# Sheet4.net
KiCad netlist of a schematic drawn in Altium Designer
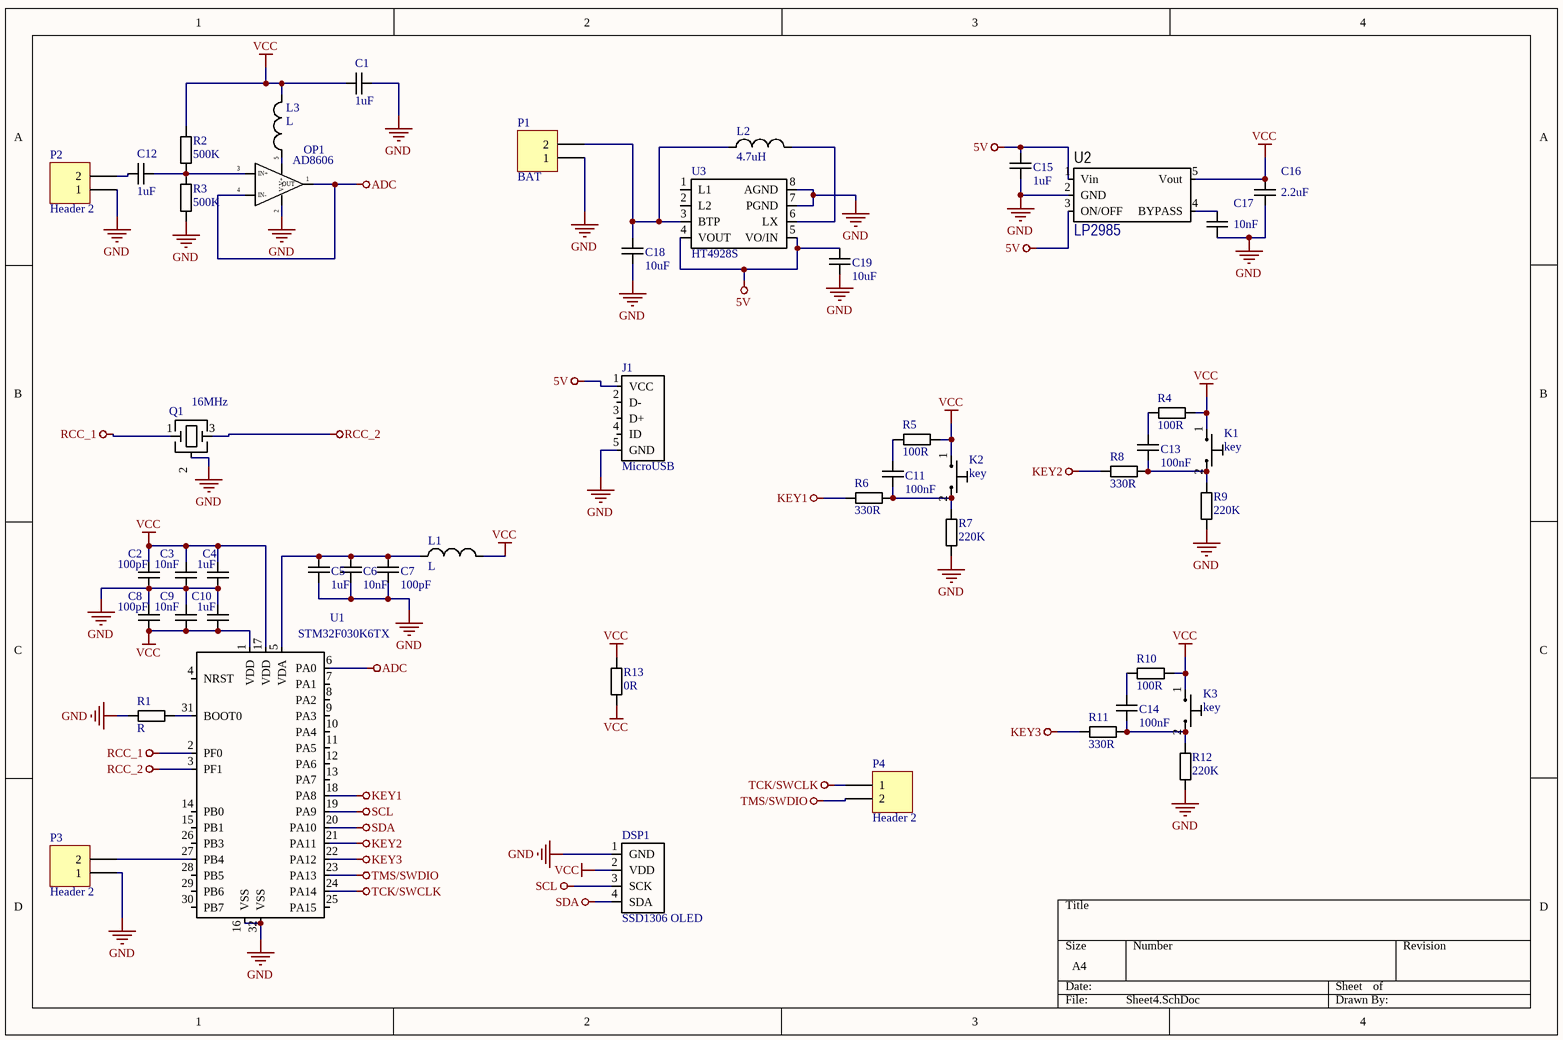
[diagram p0: Sheet4.SchDoc]

(export (version "E")
  (design (tool "Eeschema 10.0.6"))
  (components
    (comp (ref "C1") (value "1uF") (footprint "SMD-0402C") (libsource (lib "Schlib2") (part "С")))
    (comp (ref "C2") (value "100pF") (footprint "SMD-0402C") (libsource (lib "Schlib2") (part "С")))
    (comp (ref "C3") (value "10nF") (footprint "SMD-0402C") (libsource (lib "Schlib2") (part "С")))
    (comp (ref "C4") (value "1uF") (footprint "SMD-0402C") (libsource (lib "Schlib2") (part "С")))
    (comp (ref "C5") (value "1uF") (footprint "SMD-0402C") (libsource (lib "Schlib2") (part "С")))
    (comp (ref "C6") (value "10nF") (footprint "SMD-0402C") (libsource (lib "Schlib2") (part "С")))
    (comp (ref "C7") (value "100pF") (footprint "SMD-0402C") (libsource (lib "Schlib2") (part "С")))
    (comp (ref "C8") (value "100pF") (footprint "SMD-0402C") (libsource (lib "Schlib2") (part "С")))
    (comp (ref "C9") (value "10nF") (footprint "SMD-0402C") (libsource (lib "Schlib2") (part "С")))
    (comp (ref "C10") (value "1uF") (footprint "SMD-0402C") (libsource (lib "Schlib2") (part "С")))
    (comp (ref "C11") (value "100nF") (footprint "SMD-0402C") (libsource (lib "Schlib2") (part "С")))
    (comp (ref "C12") (value "1uF") (footprint "SMD-0402C") (libsource (lib "Schlib2") (part "С")))
    (comp (ref "C13") (value "100nF") (footprint "SMD-0402C") (libsource (lib "Schlib2") (part "С")))
    (comp (ref "C14") (value "100nF") (footprint "SMD-0402C") (libsource (lib "Schlib2") (part "С")))
    (comp (ref "C15") (value "1uF") (footprint "SMD-0402C") (libsource (lib "Schlib2") (part "С")))
    (comp (ref "C16") (value "2.2uF") (footprint "SMD-0402C") (libsource (lib "Schlib2") (part "С")))
    (comp (ref "C17") (value "10nF") (footprint "SMD-0402C") (libsource (lib "Schlib2") (part "С")))
    (comp (ref "C18") (value "10uF") (footprint "SMD-0805C") (libsource (lib "Schlib2") (part "С")))
    (comp (ref "C19") (value "10uF") (footprint "SMD-0805C") (libsource (lib "Schlib2") (part "С")))
    (comp (ref "DSP1")
      (value "SSD1306 OLED")
      (footprint "SSD1306")
      (libsource (lib "Schlib2") (part "SSD1306_OLED"))
    )
    (comp (ref "J1")
      (value "MicroUSB")
      (footprint "Micro USB")
      (libsource (lib "Schlib2") (part "Micro_USB_female"))
    )
    (comp (ref "K1") (value "key") (footprint "KEY") (libsource (lib "Schlib2") (part "KEY")))
    (comp (ref "K2") (value "key") (footprint "KEY") (libsource (lib "Schlib2") (part "KEY")))
    (comp (ref "K3") (value "key") (footprint "KEY") (libsource (lib "Schlib2") (part "KEY")))
    (comp (ref "L1") (value "L") (footprint "L_0805") (libsource (lib "Schlib2") (part "L")))
    (comp (ref "L2") (value "4.7uH") (footprint "CD43") (libsource (lib "Schlib2") (part "L")))
    (comp (ref "L3") (value "L") (footprint "L_0805") (libsource (lib "Schlib2") (part "L")))
    (comp (ref "OP1") (value "AD8606") (footprint "SOT-23-5") (libsource (lib "Schlib2") (part "AD8605")))
    (comp (ref "P1")
      (value "BAT")
      (footprint "MHDR1X2")
      (description "Header, 2-Pin")
      (fields (field (name "PUBLISHER") "Altium Limited"))
      (libsource (lib "Miscellaneous Connectors") (part "MHDR1X2"))
    )
    (comp (ref "P2")
      (value "Header 2")
      (footprint "HDR1X2")
      (description "Header, 2-Pin")
      (fields (field (name "PUBLISHER") "Altium Limited"))
      (libsource (lib "Miscellaneous Connectors") (part "Header 2"))
    )
    (comp (ref "P3")
      (value "Header 2")
      (footprint "HDR1X2")
      (description "Header, 2-Pin")
      (fields (field (name "PUBLISHER") "Altium Limited"))
      (libsource (lib "Miscellaneous Connectors") (part "Header 2"))
    )
    (comp (ref "P4")
      (value "Header 2")
      (footprint "HDR1X2")
      (description "Header, 2-Pin")
      (fields (field (name "PUBLISHER") "Altium Limited"))
      (libsource (lib "") (part "Header 2_1"))
    )
    (comp (ref "Q1")
      (value "16MHz")
      (footprint "Murata Ceramic Resonator")
      (libsource (lib "Schlib2") (part "Crystal_3"))
    )
    (comp (ref "R1") (value "R") (footprint "SMD-0402-RES") (libsource (lib "Schlib2") (part "R")))
    (comp (ref "R2") (value "500K") (footprint "SMD-0402-RES") (libsource (lib "Schlib2") (part "R")))
    (comp (ref "R3") (value "500K") (footprint "SMD-0402-RES") (libsource (lib "Schlib2") (part "R")))
    (comp (ref "R4") (value "100R") (footprint "SMD-0402-RES") (libsource (lib "Schlib2") (part "R")))
    (comp (ref "R5") (value "100R") (footprint "SMD-0402-RES") (libsource (lib "Schlib2") (part "R")))
    (comp (ref "R6") (value "330R") (footprint "SMD-0402-RES") (libsource (lib "Schlib2") (part "R")))
    (comp (ref "R7") (value "220K") (footprint "SMD-0402-RES") (libsource (lib "Schlib2") (part "R")))
    (comp (ref "R8") (value "330R") (footprint "SMD-0402-RES") (libsource (lib "Schlib2") (part "R")))
    (comp (ref "R9") (value "220K") (footprint "SMD-0402-RES") (libsource (lib "Schlib2") (part "R")))
    (comp (ref "R10") (value "100R") (footprint "SMD-0402-RES") (libsource (lib "Schlib2") (part "R")))
    (comp (ref "R11") (value "330R") (footprint "SMD-0402-RES") (libsource (lib "Schlib2") (part "R")))
    (comp (ref "R12") (value "220K") (footprint "SMD-0402-RES") (libsource (lib "Schlib2") (part "R")))
    (comp (ref "R13") (value "0R") (footprint "SMD-0805-RES") (libsource (lib "Schlib2") (part "R")))
    (comp (ref "U1")
      (value "STM32F030K6TX")
      (footprint "LQFP-32")
      (libsource (lib "Schlib2") (part "STM32F030K6TX"))
    )
    (comp (ref "U2") (value "LP2985") (footprint "SOT-23-5") (libsource (lib "Schlib2") (part "LP2985")))
    (comp (ref "U3") (value "HT4928S") (footprint "SOIC8") (libsource (lib "Schlib2") (part "HT4928S")))
  )
  (nets
    (net (code "1") (name "5V") (class "Default")
      (node (ref "C15") (pin "2") (pinfunction "2_2") (pintype "passive"))
      (node (ref "C19") (pin "1") (pinfunction "1_1") (pintype "passive"))
      (node (ref "J1") (pin "1") (pinfunction "VCC_1") (pintype "passive"))
      (node (ref "U2") (pin "1") (pinfunction "Vin_1") (pintype "passive"))
      (node (ref "U2") (pin "3") (pinfunction "ON/OFF_3") (pintype "passive"))
      (node (ref "U3") (pin "4") (pinfunction "VOUT_4") (pintype "passive"))
      (node (ref "U3") (pin "5") (pinfunction "VO/IN_5") (pintype "passive"))
    )
    (net (code "2") (name "ADC") (class "Default")
      (node (ref "OP1") (pin "1") (pinfunction "OUT_1") (pintype "passive"))
      (node (ref "OP1") (pin "4") (pinfunction "IN-_4") (pintype "passive"))
      (node (ref "U1") (pin "6") (pinfunction "PA0_6") (pintype "passive"))
    )
    (net (code "3") (name "GND") (class "Default")
      (node (ref "C1") (pin "1") (pinfunction "1_1") (pintype "passive"))
      (node (ref "C10") (pin "2") (pinfunction "2_2") (pintype "passive"))
      (node (ref "C15") (pin "1") (pinfunction "1_1") (pintype "passive"))
      (node (ref "C16") (pin "1") (pinfunction "1_1") (pintype "passive"))
      (node (ref "C17") (pin "1") (pinfunction "1_1") (pintype "passive"))
      (node (ref "C18") (pin "2") (pinfunction "2_2") (pintype "passive"))
      (node (ref "C19") (pin "2") (pinfunction "2_2") (pintype "passive"))
      (node (ref "C2") (pin "1") (pinfunction "1_1") (pintype "passive"))
      (node (ref "C3") (pin "2") (pinfunction "2_2") (pintype "passive"))
      (node (ref "C4") (pin "1") (pinfunction "1_1") (pintype "passive"))
      (node (ref "C5") (pin "2") (pinfunction "2_2") (pintype "passive"))
      (node (ref "C6") (pin "1") (pinfunction "1_1") (pintype "passive"))
      (node (ref "C7") (pin "2") (pinfunction "2_2") (pintype "passive"))
      (node (ref "C8") (pin "2") (pinfunction "2_2") (pintype "passive"))
      (node (ref "C9") (pin "1") (pinfunction "1_1") (pintype "passive"))
      (node (ref "DSP1") (pin "1") (pinfunction "GND_1") (pintype "passive"))
      (node (ref "J1") (pin "5") (pinfunction "GND_5") (pintype "passive"))
      (node (ref "OP1") (pin "2") (pinfunction "V-_2") (pintype "passive"))
      (node (ref "P1") (pin "1") (pinfunction "1_1") (pintype "passive"))
      (node (ref "P2") (pin "1") (pinfunction "1_1") (pintype "passive"))
      (node (ref "P3") (pin "1") (pinfunction "1_1") (pintype "passive"))
      (node (ref "Q1") (pin "2") (pinfunction "2_2") (pintype "passive"))
      (node (ref "R1") (pin "1") (pinfunction "1_1") (pintype "passive"))
      (node (ref "R12") (pin "1") (pinfunction "1_1") (pintype "passive"))
      (node (ref "R3") (pin "1") (pinfunction "1_1") (pintype "passive"))
      (node (ref "R7") (pin "1") (pinfunction "1_1") (pintype "passive"))
      (node (ref "R9") (pin "1") (pinfunction "1_1") (pintype "passive"))
      (node (ref "U1") (pin "16") (pinfunction "VSS_16") (pintype "passive"))
      (node (ref "U1") (pin "32") (pinfunction "VSS_32") (pintype "passive"))
      (node (ref "U2") (pin "2") (pinfunction "GND_2") (pintype "passive"))
      (node (ref "U3") (pin "7") (pinfunction "PGND_7") (pintype "passive"))
      (node (ref "U3") (pin "8") (pinfunction "AGND_8") (pintype "passive"))
    )
    (net (code "4") (name "KEY1") (class "Default")
      (node (ref "R6") (pin "1") (pinfunction "1_1") (pintype "passive"))
      (node (ref "U1") (pin "18") (pinfunction "PA8_18") (pintype "passive"))
    )
    (net (code "5") (name "KEY2") (class "Default")
      (node (ref "R8") (pin "1") (pinfunction "1_1") (pintype "passive"))
      (node (ref "U1") (pin "21") (pinfunction "PA11_21") (pintype "passive"))
    )
    (net (code "6") (name "KEY3") (class "Default")
      (node (ref "R11") (pin "1") (pinfunction "1_1") (pintype "passive"))
      (node (ref "U1") (pin "22") (pinfunction "PA12_22") (pintype "passive"))
    )
    (net (code "7") (name "Net-(C11-Pad1)") (class "Default")
      (node (ref "C11") (pin "1") (pinfunction "1_1") (pintype "passive"))
      (node (ref "K2") (pin "2") (pinfunction "2_2") (pintype "passive"))
      (node (ref "R6") (pin "2") (pinfunction "2_2") (pintype "passive"))
      (node (ref "R7") (pin "2") (pinfunction "2_2") (pintype "passive"))
    )
    (net (code "8") (name "Net-(C11-Pad2)") (class "Default")
      (node (ref "C11") (pin "2") (pinfunction "2_2") (pintype "passive"))
      (node (ref "R5") (pin "1") (pinfunction "1_1") (pintype "passive"))
    )
    (net (code "9") (name "Net-(C12-Pad2)") (class "Default")
      (node (ref "C12") (pin "2") (pinfunction "2_2") (pintype "passive"))
      (node (ref "P2") (pin "2") (pinfunction "2_2") (pintype "passive"))
    )
    (net (code "10") (name "Net-(C13-Pad1)") (class "Default")
      (node (ref "C13") (pin "1") (pinfunction "1_1") (pintype "passive"))
      (node (ref "K1") (pin "2") (pinfunction "2_2") (pintype "passive"))
      (node (ref "R8") (pin "2") (pinfunction "2_2") (pintype "passive"))
      (node (ref "R9") (pin "2") (pinfunction "2_2") (pintype "passive"))
    )
    (net (code "11") (name "Net-(C13-Pad2)") (class "Default")
      (node (ref "C13") (pin "2") (pinfunction "2_2") (pintype "passive"))
      (node (ref "R4") (pin "1") (pinfunction "1_1") (pintype "passive"))
    )
    (net (code "12") (name "Net-(C14-Pad1)") (class "Default")
      (node (ref "C14") (pin "1") (pinfunction "1_1") (pintype "passive"))
      (node (ref "K3") (pin "2") (pinfunction "2_2") (pintype "passive"))
      (node (ref "R11") (pin "2") (pinfunction "2_2") (pintype "passive"))
      (node (ref "R12") (pin "2") (pinfunction "2_2") (pintype "passive"))
    )
    (net (code "13") (name "Net-(C14-Pad2)") (class "Default")
      (node (ref "C14") (pin "2") (pinfunction "2_2") (pintype "passive"))
      (node (ref "R10") (pin "1") (pinfunction "1_1") (pintype "passive"))
    )
    (net (code "14") (name "Net-(L1-4)") (class "Default")
      (node (ref "C5") (pin "1") (pinfunction "1_1") (pintype "passive"))
      (node (ref "C6") (pin "2") (pinfunction "2_2") (pintype "passive"))
      (node (ref "C7") (pin "1") (pinfunction "1_1") (pintype "passive"))
      (node (ref "L1") (pin "1") (pinfunction "4_1") (pintype "passive"))
      (node (ref "U1") (pin "5") (pinfunction "VDA_5") (pintype "passive"))
    )
    (net (code "15") (name "Net-(L2-4)") (class "Default")
      (node (ref "C18") (pin "1") (pinfunction "1_1") (pintype "passive"))
      (node (ref "L2") (pin "1") (pinfunction "4_1") (pintype "passive"))
      (node (ref "P1") (pin "2") (pinfunction "2_2") (pintype "passive"))
      (node (ref "U3") (pin "3") (pinfunction "BTP_3") (pintype "passive"))
    )
    (net (code "16") (name "Net-(L3-4)") (class "Default")
      (node (ref "L3") (pin "1") (pinfunction "4_1") (pintype "passive"))
      (node (ref "OP1") (pin "5") (pinfunction "V+_5") (pintype "passive"))
    )
    (net (code "17") (name "Net-(OP1-IN+)") (class "Default")
      (node (ref "C12") (pin "1") (pinfunction "1_1") (pintype "passive"))
      (node (ref "OP1") (pin "3") (pinfunction "IN+_3") (pintype "passive"))
      (node (ref "R2") (pin "1") (pinfunction "1_1") (pintype "passive"))
      (node (ref "R3") (pin "2") (pinfunction "2_2") (pintype "passive"))
    )
    (net (code "18") (name "Net-(U1-BOOT0)") (class "Default")
      (node (ref "R1") (pin "2") (pinfunction "2_2") (pintype "passive"))
      (node (ref "U1") (pin "31") (pinfunction "BOOT0_31") (pintype "passive"))
    )
    (net (code "19") (name "Net-(U1-PB4)") (class "Default")
      (node (ref "P3") (pin "2") (pinfunction "2_2") (pintype "passive"))
      (node (ref "U1") (pin "27") (pinfunction "PB4_27") (pintype "passive"))
    )
    (net (code "20") (name "Net-(U2-BYPASS)") (class "Default")
      (node (ref "C17") (pin "2") (pinfunction "2_2") (pintype "passive"))
      (node (ref "U2") (pin "4") (pinfunction "BYPASS_4") (pintype "passive"))
    )
    (net (code "21") (name "Net-(U3-LX)") (class "Default")
      (node (ref "L2") (pin "2") (pinfunction "2_2") (pintype "passive"))
      (node (ref "U3") (pin "6") (pinfunction "LX_6") (pintype "passive"))
    )
    (net (code "22") (name "RCC_1") (class "Default")
      (node (ref "Q1") (pin "1") (pinfunction "1_1") (pintype "passive"))
      (node (ref "U1") (pin "2") (pinfunction "PF0_2") (pintype "passive"))
    )
    (net (code "23") (name "RCC_2") (class "Default")
      (node (ref "Q1") (pin "3") (pinfunction "3_3") (pintype "passive"))
      (node (ref "U1") (pin "3") (pinfunction "PF1_3") (pintype "passive"))
    )
    (net (code "24") (name "SCL") (class "Default")
      (node (ref "DSP1") (pin "3") (pinfunction "SCK_3") (pintype "passive"))
      (node (ref "U1") (pin "19") (pinfunction "PA9_19") (pintype "passive"))
    )
    (net (code "25") (name "SDA") (class "Default")
      (node (ref "DSP1") (pin "4") (pinfunction "SDA_4") (pintype "passive"))
      (node (ref "U1") (pin "20") (pinfunction "PA10_20") (pintype "passive"))
    )
    (net (code "26") (name "TCK{slash}SWCLK") (class "Default")
      (node (ref "P4") (pin "1") (pinfunction "1_1") (pintype "passive"))
      (node (ref "U1") (pin "24") (pinfunction "PA14_24") (pintype "passive"))
    )
    (net (code "27") (name "TMS{slash}SWDIO") (class "Default")
      (node (ref "P4") (pin "2") (pinfunction "2_2") (pintype "passive"))
      (node (ref "U1") (pin "23") (pinfunction "PA13_23") (pintype "passive"))
    )
    (net (code "28") (name "VCC") (class "Default")
      (node (ref "C1") (pin "2") (pinfunction "2_2") (pintype "passive"))
      (node (ref "C10") (pin "1") (pinfunction "1_1") (pintype "passive"))
      (node (ref "C16") (pin "2") (pinfunction "2_2") (pintype "passive"))
      (node (ref "C2") (pin "2") (pinfunction "2_2") (pintype "passive"))
      (node (ref "C3") (pin "1") (pinfunction "1_1") (pintype "passive"))
      (node (ref "C4") (pin "2") (pinfunction "2_2") (pintype "passive"))
      (node (ref "C8") (pin "1") (pinfunction "1_1") (pintype "passive"))
      (node (ref "C9") (pin "2") (pinfunction "2_2") (pintype "passive"))
      (node (ref "DSP1") (pin "2") (pinfunction "VDD_2") (pintype "passive"))
      (node (ref "K1") (pin "1") (pinfunction "1_1") (pintype "passive"))
      (node (ref "K2") (pin "1") (pinfunction "1_1") (pintype "passive"))
      (node (ref "K3") (pin "1") (pinfunction "1_1") (pintype "passive"))
      (node (ref "L1") (pin "2") (pinfunction "2_2") (pintype "passive"))
      (node (ref "L3") (pin "2") (pinfunction "2_2") (pintype "passive"))
      (node (ref "R10") (pin "2") (pinfunction "2_2") (pintype "passive"))
      (node (ref "R13") (pin "1") (pinfunction "1_1") (pintype "passive"))
      (node (ref "R13") (pin "2") (pinfunction "2_2") (pintype "passive"))
      (node (ref "R2") (pin "2") (pinfunction "2_2") (pintype "passive"))
      (node (ref "R4") (pin "2") (pinfunction "2_2") (pintype "passive"))
      (node (ref "R5") (pin "2") (pinfunction "2_2") (pintype "passive"))
      (node (ref "U1") (pin "1") (pinfunction "VDD_1") (pintype "passive"))
      (node (ref "U1") (pin "17") (pinfunction "VDD_17") (pintype "passive"))
      (node (ref "U2") (pin "5") (pinfunction "Vout_5") (pintype "passive"))
    )
    (net (code "29") (name "unconnected-(J1-D+-Pad3)") (class "Default")
      (node (ref "J1") (pin "3") (pinfunction "D+_3") (pintype "passive"))
    )
    (net (code "30") (name "unconnected-(J1-D--Pad2)") (class "Default")
      (node (ref "J1") (pin "2") (pinfunction "D-_2") (pintype "passive"))
    )
    (net (code "31") (name "unconnected-(J1-ID-Pad4)") (class "Default")
      (node (ref "J1") (pin "4") (pinfunction "ID_4") (pintype "passive"))
    )
    (net (code "32") (name "unconnected-(U1-NRST-Pad4)") (class "Default")
      (node (ref "U1") (pin "4") (pinfunction "NRST_4") (pintype "passive"))
    )
    (net (code "33") (name "unconnected-(U1-PA1-Pad7)") (class "Default")
      (node (ref "U1") (pin "7") (pinfunction "PA1_7") (pintype "passive"))
    )
    (net (code "34") (name "unconnected-(U1-PA2-Pad8)") (class "Default")
      (node (ref "U1") (pin "8") (pinfunction "PA2_8") (pintype "passive"))
    )
    (net (code "35") (name "unconnected-(U1-PA3-Pad9)") (class "Default")
      (node (ref "U1") (pin "9") (pinfunction "PA3_9") (pintype "passive"))
    )
    (net (code "36") (name "unconnected-(U1-PA4-Pad10)") (class "Default")
      (node (ref "U1") (pin "10") (pinfunction "PA4_10") (pintype "passive"))
    )
    (net (code "37") (name "unconnected-(U1-PA5-Pad11)") (class "Default")
      (node (ref "U1") (pin "11") (pinfunction "PA5_11") (pintype "passive"))
    )
    (net (code "38") (name "unconnected-(U1-PA6-Pad12)") (class "Default")
      (node (ref "U1") (pin "12") (pinfunction "PA6_12") (pintype "passive"))
    )
    (net (code "39") (name "unconnected-(U1-PA7-Pad13)") (class "Default")
      (node (ref "U1") (pin "13") (pinfunction "PA7_13") (pintype "passive"))
    )
    (net (code "40") (name "unconnected-(U1-PA15-Pad25)") (class "Default")
      (node (ref "U1") (pin "25") (pinfunction "PA15_25") (pintype "passive"))
    )
    (net (code "41") (name "unconnected-(U1-PB0-Pad14)") (class "Default")
      (node (ref "U1") (pin "14") (pinfunction "PB0_14") (pintype "passive"))
    )
    (net (code "42") (name "unconnected-(U1-PB1-Pad15)") (class "Default")
      (node (ref "U1") (pin "15") (pinfunction "PB1_15") (pintype "passive"))
    )
    (net (code "43") (name "unconnected-(U1-PB3-Pad26)") (class "Default")
      (node (ref "U1") (pin "26") (pinfunction "PB3_26") (pintype "passive"))
    )
    (net (code "44") (name "unconnected-(U1-PB5-Pad28)") (class "Default")
      (node (ref "U1") (pin "28") (pinfunction "PB5_28") (pintype "passive"))
    )
    (net (code "45") (name "unconnected-(U1-PB6-Pad29)") (class "Default")
      (node (ref "U1") (pin "29") (pinfunction "PB6_29") (pintype "passive"))
    )
    (net (code "46") (name "unconnected-(U1-PB7-Pad30)") (class "Default")
      (node (ref "U1") (pin "30") (pinfunction "PB7_30") (pintype "passive"))
    )
    (net (code "47") (name "unconnected-(U3-L1-Pad1)") (class "Default")
      (node (ref "U3") (pin "1") (pinfunction "L1_1") (pintype "passive"))
    )
    (net (code "48") (name "unconnected-(U3-L2-Pad2)") (class "Default")
      (node (ref "U3") (pin "2") (pinfunction "L2_2") (pintype "passive"))
    )
  )
)
